# PowerSupply.net
KiCad netlist of a schematic drawn in Altium Designer
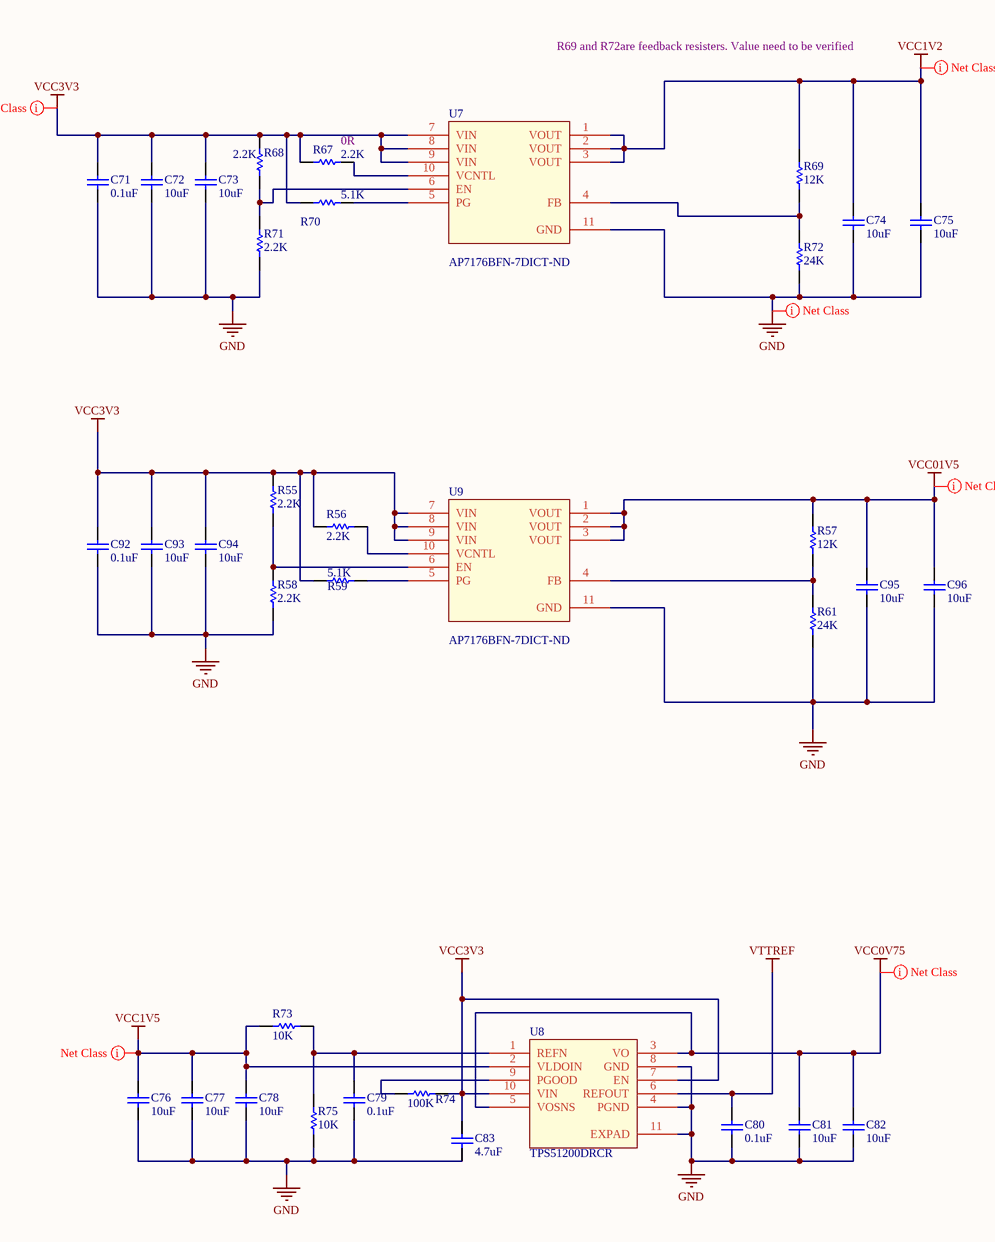
[diagram p0: PowerSupply.SchDoc]

(export (version "E")
  (design (tool "Eeschema 10.0.6"))
  (components
    (comp (ref "C71")
      (value "0.1uF")
      (footprint "0402")
      (description "Capacitor (Semiconductor SIM Model)")
      (fields (field (name "Comment") "Cap Semi") (field (name "PUBLISHER") "Altium Limited"))
      (libsource (lib "Miscellaneous Devices") (part "Cap Semi"))
    )
    (comp (ref "C72")
      (value "10uF")
      (footprint "1608[0603]")
      (description "Capacitor (Semiconductor SIM Model)")
      (fields (field (name "Comment") "Cap Semi") (field (name "PUBLISHER") "Altium Limited"))
      (libsource (lib "Miscellaneous Devices") (part "Cap Semi"))
    )
    (comp (ref "C73")
      (value "10uF")
      (footprint "1608[0603]")
      (description "Capacitor (Semiconductor SIM Model)")
      (fields (field (name "Comment") "Cap Semi") (field (name "PUBLISHER") "Altium Limited"))
      (libsource (lib "Miscellaneous Devices") (part "Cap Semi"))
    )
    (comp (ref "C74")
      (value "10uF")
      (footprint "C0805")
      (description "Capacitor (Semiconductor SIM Model)")
      (fields (field (name "Comment") "Cap Semi") (field (name "PUBLISHER") "Altium Limited"))
      (libsource (lib "Miscellaneous Devices") (part "Cap Semi"))
    )
    (comp (ref "C75")
      (value "10uF")
      (footprint "C0805")
      (description "Capacitor (Semiconductor SIM Model)")
      (fields (field (name "Comment") "Cap Semi") (field (name "PUBLISHER") "Altium Limited"))
      (libsource (lib "Miscellaneous Devices") (part "Cap Semi"))
    )
    (comp (ref "C76")
      (value "10uF")
      (footprint "1608[0603]")
      (description "Capacitor (Semiconductor SIM Model)")
      (fields (field (name "Comment") "Cap Semi") (field (name "PUBLISHER") "Altium Limited"))
      (libsource (lib "Miscellaneous Devices") (part "Cap Semi"))
    )
    (comp (ref "C77")
      (value "10uF")
      (footprint "1608[0603]")
      (description "Capacitor (Semiconductor SIM Model)")
      (fields (field (name "Comment") "Cap Semi") (field (name "PUBLISHER") "Altium Limited"))
      (libsource (lib "Miscellaneous Devices") (part "Cap Semi"))
    )
    (comp (ref "C78")
      (value "10uF")
      (footprint "0402")
      (description "Capacitor (Semiconductor SIM Model)")
      (fields (field (name "Comment") "Cap Semi") (field (name "PUBLISHER") "Altium Limited"))
      (libsource (lib "Miscellaneous Devices") (part "Cap Semi"))
    )
    (comp (ref "C79")
      (value "0.1uF")
      (footprint "0402")
      (description "Capacitor (Semiconductor SIM Model)")
      (fields (field (name "Comment") "Cap Semi") (field (name "PUBLISHER") "Altium Limited"))
      (libsource (lib "Miscellaneous Devices") (part "Cap Semi"))
    )
    (comp (ref "C80")
      (value "0.1uF")
      (footprint "0402")
      (description "Capacitor (Semiconductor SIM Model)")
      (fields (field (name "Comment") "Cap Semi") (field (name "PUBLISHER") "Altium Limited"))
      (libsource (lib "Miscellaneous Devices") (part "Cap Semi"))
    )
    (comp (ref "C81")
      (value "10uF")
      (footprint "0402")
      (description "Capacitor (Semiconductor SIM Model)")
      (fields (field (name "Comment") "Cap Semi") (field (name "PUBLISHER") "Altium Limited"))
      (libsource (lib "Miscellaneous Devices") (part "Cap Semi"))
    )
    (comp (ref "C82")
      (value "10uF")
      (footprint "C0805")
      (description "Capacitor (Semiconductor SIM Model)")
      (fields (field (name "Comment") "Cap Semi") (field (name "PUBLISHER") "Altium Limited"))
      (libsource (lib "Miscellaneous Devices") (part "Cap Semi"))
    )
    (comp (ref "C83")
      (value "4.7uF")
      (footprint "0402")
      (description "Capacitor (Semiconductor SIM Model)")
      (fields (field (name "Comment") "Cap Semi") (field (name "PUBLISHER") "Altium Limited"))
      (libsource (lib "Miscellaneous Devices") (part "Cap Semi"))
    )
    (comp (ref "C92")
      (value "0.1uF")
      (footprint "0402")
      (description "Capacitor")
      (fields (field (name "Comment") "Cap") (field (name "PUBLISHER") "Altium Limited"))
      (libsource (lib "Miscellaneous Devices") (part "Cap"))
    )
    (comp (ref "C93")
      (value "10uF")
      (footprint "1608[0603]")
      (description "Capacitor")
      (fields (field (name "Comment") "Cap") (field (name "PUBLISHER") "Altium Limited"))
      (libsource (lib "Miscellaneous Devices") (part "Cap"))
    )
    (comp (ref "C94")
      (value "10uF")
      (footprint "1608[0603]")
      (description "Capacitor")
      (fields (field (name "Comment") "Cap") (field (name "PUBLISHER") "Altium Limited"))
      (libsource (lib "Miscellaneous Devices") (part "Cap"))
    )
    (comp (ref "C95")
      (value "10uF")
      (footprint "1608[0603]")
      (description "Capacitor")
      (fields (field (name "Comment") "Cap") (field (name "PUBLISHER") "Altium Limited"))
      (libsource (lib "Miscellaneous Devices") (part "Cap"))
    )
    (comp (ref "C96")
      (value "10uF")
      (footprint "1608[0603]")
      (description "Capacitor")
      (fields (field (name "Comment") "Cap") (field (name "PUBLISHER") "Altium Limited"))
      (libsource (lib "Miscellaneous Devices") (part "Cap"))
    )
    (comp (ref "R55")
      (value "2.2K")
      (description "Semiconductor Resistor")
      (fields (field (name "Comment") "Res Semi") (field (name "PUBLISHER") "Altium Limited"))
      (libsource (lib "Miscellaneous Devices") (part "Res Semi"))
    )
    (comp (ref "R56")
      (value "2.2K")
      (description "Semiconductor Resistor")
      (fields (field (name "Comment") "Res Semi") (field (name "PUBLISHER") "Altium Limited"))
      (libsource (lib "Miscellaneous Devices") (part "Res Semi"))
    )
    (comp (ref "R57")
      (value "12K")
      (description "Semiconductor Resistor")
      (fields (field (name "Comment") "Res Semi") (field (name "PUBLISHER") "Altium Limited"))
      (libsource (lib "Miscellaneous Devices") (part "Res Semi"))
    )
    (comp (ref "R58")
      (value "2.2K")
      (description "Semiconductor Resistor")
      (fields (field (name "Comment") "Res Semi") (field (name "PUBLISHER") "Altium Limited"))
      (libsource (lib "Miscellaneous Devices") (part "Res Semi"))
    )
    (comp (ref "R59")
      (value "5.1K")
      (description "Semiconductor Resistor")
      (fields (field (name "Comment") "Res Semi") (field (name "PUBLISHER") "Altium Limited"))
      (libsource (lib "Miscellaneous Devices") (part "Res Semi"))
    )
    (comp (ref "R61")
      (value "24K")
      (description "Semiconductor Resistor")
      (fields (field (name "Comment") "Res Semi") (field (name "PUBLISHER") "Altium Limited"))
      (libsource (lib "Miscellaneous Devices") (part "Res Semi"))
    )
    (comp (ref "R67")
      (value "2.2K")
      (footprint "0402")
      (description "Semiconductor Resistor")
      (fields (field (name "Comment") "Res Semi") (field (name "PUBLISHER") "Altium Limited"))
      (libsource (lib "Miscellaneous Devices") (part "Res Semi"))
    )
    (comp (ref "R68")
      (value "2.2K")
      (footprint "0402")
      (description "Semiconductor Resistor")
      (fields (field (name "Comment") "Res Semi") (field (name "PUBLISHER") "Altium Limited"))
      (libsource (lib "Miscellaneous Devices") (part "Res Semi"))
    )
    (comp (ref "R69")
      (value "12K")
      (footprint "0402")
      (description "Semiconductor Resistor")
      (fields (field (name "Comment") "Res Semi") (field (name "PUBLISHER") "Altium Limited"))
      (libsource (lib "Miscellaneous Devices") (part "Res Semi"))
    )
    (comp (ref "R70")
      (value "5.1K")
      (footprint "0402")
      (description "Semiconductor Resistor")
      (fields (field (name "Comment") "Res Semi") (field (name "PUBLISHER") "Altium Limited"))
      (libsource (lib "Miscellaneous Devices") (part "Res Semi"))
    )
    (comp (ref "R71")
      (value "2.2K")
      (description "Semiconductor Resistor")
      (fields (field (name "Comment") "Res Semi") (field (name "PUBLISHER") "Altium Limited"))
      (libsource (lib "Miscellaneous Devices") (part "Res Semi"))
    )
    (comp (ref "R72")
      (value "24K")
      (footprint "0402")
      (description "Semiconductor Resistor")
      (fields (field (name "Comment") "Res Semi") (field (name "PUBLISHER") "Altium Limited"))
      (libsource (lib "Miscellaneous Devices") (part "Res Semi"))
    )
    (comp (ref "R73")
      (value "10K")
      (footprint "0402")
      (description "Semiconductor Resistor")
      (fields (field (name "Comment") "Res Semi") (field (name "PUBLISHER") "Altium Limited"))
      (libsource (lib "Miscellaneous Devices") (part "Res Semi"))
    )
    (comp (ref "R74")
      (value "100K")
      (footprint "0402")
      (description "Semiconductor Resistor")
      (fields (field (name "Comment") "Res Semi") (field (name "PUBLISHER") "Altium Limited"))
      (libsource (lib "Miscellaneous Devices") (part "Res Semi"))
    )
    (comp (ref "R75")
      (value "10K")
      (footprint "0402")
      (description "Semiconductor Resistor")
      (fields (field (name "Comment") "Res Semi") (field (name "PUBLISHER") "Altium Limited"))
      (libsource (lib "Miscellaneous Devices") (part "Res Semi"))
    )
    (comp (ref "U7")
      (value "AP7176BFN-7DICT-ND")
      (footprint "PSON50P300X100_HS-11N")
      (description "IC REG LDO ADJ 3A 10-DFN")
      (fields
        (field (name "MANUFACTURER") "Diodes Incorporated")
        (field (name "MANUFACTURER PART NUMBER") "AP7176BFN-7")
        (field (name "SUPPLIER PART NUMBER 1") "AP7176BFN-7DICT-ND")
      )
      (libsource (lib "PolySomeCrypto01") (part "AP7176BFN-7"))
    )
    (comp (ref "U8")
      (value "TPS51200DRCR")
      (footprint "PSON50P300X100_HS-11N")
      (description "IC CONV DDR DDR2 DDR3 10SON")
      (fields (field (name "MANUFACTURER") "Texas Instruments"))
      (libsource (lib "PolySomeCrypto01") (part "TPS51200DRCR"))
    )
    (comp (ref "U9")
      (value "AP7176BFN-7DICT-ND")
      (footprint "PSON50P300X100_HS-11N")
      (description "IC REG LDO ADJ 3A 10-DFN")
      (fields
        (field (name "MANUFACTURER") "Diodes Incorporated")
        (field (name "MANUFACTURER PART NUMBER") "AP7176BFN-7")
        (field (name "SUPPLIER PART NUMBER 1") "AP7176BFN-7DICT-ND")
      )
      (libsource (lib "PolySomeCrypto01") (part "AP7176BFN-7"))
    )
  )
  (nets
    (net (code "1") (name "GND") (class "Default")
      (node (ref "C71") (pin "2") (pinfunction "2_2") (pintype "passive"))
      (node (ref "C72") (pin "2") (pinfunction "2_2") (pintype "passive"))
      (node (ref "C73") (pin "2") (pinfunction "2_2") (pintype "passive"))
      (node (ref "C74") (pin "2") (pinfunction "2_2") (pintype "passive"))
      (node (ref "C75") (pin "2") (pinfunction "2_2") (pintype "passive"))
      (node (ref "C76") (pin "2") (pinfunction "2_2") (pintype "passive"))
      (node (ref "C77") (pin "2") (pinfunction "2_2") (pintype "passive"))
      (node (ref "C78") (pin "2") (pinfunction "2_2") (pintype "passive"))
      (node (ref "C79") (pin "2") (pinfunction "2_2") (pintype "passive"))
      (node (ref "C80") (pin "2") (pinfunction "2_2") (pintype "passive"))
      (node (ref "C81") (pin "2") (pinfunction "2_2") (pintype "passive"))
      (node (ref "C82") (pin "2") (pinfunction "2_2") (pintype "passive"))
      (node (ref "C83") (pin "2") (pinfunction "2_2") (pintype "passive"))
      (node (ref "C92") (pin "1") (pinfunction "1_1") (pintype "passive"))
      (node (ref "C93") (pin "1") (pinfunction "1_1") (pintype "passive"))
      (node (ref "C94") (pin "1") (pinfunction "1_1") (pintype "passive"))
      (node (ref "C95") (pin "1") (pinfunction "1_1") (pintype "passive"))
      (node (ref "C96") (pin "1") (pinfunction "1_1") (pintype "passive"))
      (node (ref "R58") (pin "1") (pinfunction "1_1") (pintype "passive"))
      (node (ref "R61") (pin "1") (pinfunction "1_1") (pintype "passive"))
      (node (ref "R71") (pin "1") (pinfunction "1_1") (pintype "passive"))
      (node (ref "R72") (pin "1") (pinfunction "1_1") (pintype "passive"))
      (node (ref "R75") (pin "1") (pinfunction "1_1") (pintype "passive"))
      (node (ref "U7") (pin "11") (pinfunction "GND_11") (pintype "power_in"))
      (node (ref "U8") (pin "11") (pinfunction "EXPAD_11") (pintype "power_in"))
      (node (ref "U8") (pin "4") (pinfunction "PGND_4") (pintype "power_in"))
      (node (ref "U8") (pin "8") (pinfunction "GND_8") (pintype "power_in"))
      (node (ref "U9") (pin "11") (pinfunction "GND_11") (pintype "power_in"))
    )
    (net (code "2") (name "Net-(U7-EN)") (class "Default")
      (node (ref "R68") (pin "1") (pinfunction "1_1") (pintype "passive"))
      (node (ref "R71") (pin "2") (pinfunction "2_2") (pintype "passive"))
      (node (ref "U7") (pin "6") (pinfunction "EN_6") (pintype "power_in"))
    )
    (net (code "3") (name "Net-(U7-FB)") (class "Default")
      (node (ref "R69") (pin "1") (pinfunction "1_1") (pintype "passive"))
      (node (ref "R72") (pin "2") (pinfunction "2_2") (pintype "passive"))
      (node (ref "U7") (pin "4") (pinfunction "FB_4") (pintype "power_in"))
    )
    (net (code "4") (name "Net-(U7-PG)") (class "Default")
      (node (ref "R70") (pin "2") (pinfunction "2_2") (pintype "passive"))
      (node (ref "U7") (pin "5") (pinfunction "PG_5") (pintype "open_collector"))
    )
    (net (code "5") (name "Net-(U7-VCNTL)") (class "Default")
      (node (ref "R67") (pin "2") (pinfunction "2_2") (pintype "passive"))
      (node (ref "U7") (pin "10") (pinfunction "VCNTL_10") (pintype "power_in"))
    )
    (net (code "6") (name "Net-(U8-PGOOD)") (class "Default")
      (node (ref "R74") (pin "1") (pinfunction "1_1") (pintype "passive"))
      (node (ref "U8") (pin "9") (pinfunction "PGOOD_9") (pintype "power_in"))
    )
    (net (code "7") (name "Net-(U8-REFN)") (class "Default")
      (node (ref "C79") (pin "1") (pinfunction "1_1") (pintype "passive"))
      (node (ref "R73") (pin "2") (pinfunction "2_2") (pintype "passive"))
      (node (ref "R75") (pin "2") (pinfunction "2_2") (pintype "passive"))
      (node (ref "U8") (pin "1") (pinfunction "REFN_1") (pintype "power_in"))
    )
    (net (code "8") (name "Net-(U9-EN)") (class "Default")
      (node (ref "R55") (pin "1") (pinfunction "1_1") (pintype "passive"))
      (node (ref "R58") (pin "2") (pinfunction "2_2") (pintype "passive"))
      (node (ref "U9") (pin "6") (pinfunction "EN_6") (pintype "power_in"))
    )
    (net (code "9") (name "Net-(U9-FB)") (class "Default")
      (node (ref "R57") (pin "1") (pinfunction "1_1") (pintype "passive"))
      (node (ref "R61") (pin "2") (pinfunction "2_2") (pintype "passive"))
      (node (ref "U9") (pin "4") (pinfunction "FB_4") (pintype "power_in"))
    )
    (net (code "10") (name "Net-(U9-PG)") (class "Default")
      (node (ref "R59") (pin "1") (pinfunction "1_1") (pintype "passive"))
      (node (ref "U9") (pin "5") (pinfunction "PG_5") (pintype "open_collector"))
    )
    (net (code "11") (name "Net-(U9-VCNTL)") (class "Default")
      (node (ref "R56") (pin "1") (pinfunction "1_1") (pintype "passive"))
      (node (ref "U9") (pin "10") (pinfunction "VCNTL_10") (pintype "power_in"))
    )
    (net (code "12") (name "VCC0V75") (class "Default")
      (node (ref "C81") (pin "1") (pinfunction "1_1") (pintype "passive"))
      (node (ref "C82") (pin "1") (pinfunction "1_1") (pintype "passive"))
      (node (ref "U8") (pin "3") (pinfunction "VO_3") (pintype "power_in"))
      (node (ref "U8") (pin "5") (pinfunction "VOSNS_5") (pintype "power_in"))
    )
    (net (code "13") (name "VCC1V2") (class "Default")
      (node (ref "C74") (pin "1") (pinfunction "1_1") (pintype "passive"))
      (node (ref "C75") (pin "1") (pinfunction "1_1") (pintype "passive"))
      (node (ref "R69") (pin "2") (pinfunction "2_2") (pintype "passive"))
      (node (ref "U7") (pin "1") (pinfunction "VOUT_1") (pintype "power_in"))
      (node (ref "U7") (pin "2") (pinfunction "VOUT_2") (pintype "power_in"))
      (node (ref "U7") (pin "3") (pinfunction "VOUT_3") (pintype "power_in"))
    )
    (net (code "14") (name "VCC1V5") (class "Default")
      (node (ref "C76") (pin "1") (pinfunction "1_1") (pintype "passive"))
      (node (ref "C77") (pin "1") (pinfunction "1_1") (pintype "passive"))
      (node (ref "C78") (pin "1") (pinfunction "1_1") (pintype "passive"))
      (node (ref "R73") (pin "1") (pinfunction "1_1") (pintype "passive"))
      (node (ref "U8") (pin "2") (pinfunction "VLDOIN_2") (pintype "power_in"))
    )
    (net (code "15") (name "VCC01V5") (class "Default")
      (node (ref "C95") (pin "2") (pinfunction "2_2") (pintype "passive"))
      (node (ref "C96") (pin "2") (pinfunction "2_2") (pintype "passive"))
      (node (ref "R57") (pin "2") (pinfunction "2_2") (pintype "passive"))
      (node (ref "U9") (pin "1") (pinfunction "VOUT_1") (pintype "power_in"))
      (node (ref "U9") (pin "2") (pinfunction "VOUT_2") (pintype "power_in"))
      (node (ref "U9") (pin "3") (pinfunction "VOUT_3") (pintype "power_in"))
    )
    (net (code "16") (name "VCC3V3") (class "Default")
      (node (ref "C71") (pin "1") (pinfunction "1_1") (pintype "passive"))
      (node (ref "C72") (pin "1") (pinfunction "1_1") (pintype "passive"))
      (node (ref "C73") (pin "1") (pinfunction "1_1") (pintype "passive"))
      (node (ref "C83") (pin "1") (pinfunction "1_1") (pintype "passive"))
      (node (ref "C92") (pin "2") (pinfunction "2_2") (pintype "passive"))
      (node (ref "C93") (pin "2") (pinfunction "2_2") (pintype "passive"))
      (node (ref "C94") (pin "2") (pinfunction "2_2") (pintype "passive"))
      (node (ref "R55") (pin "2") (pinfunction "2_2") (pintype "passive"))
      (node (ref "R56") (pin "2") (pinfunction "2_2") (pintype "passive"))
      (node (ref "R59") (pin "2") (pinfunction "2_2") (pintype "passive"))
      (node (ref "R67") (pin "1") (pinfunction "1_1") (pintype "passive"))
      (node (ref "R68") (pin "2") (pinfunction "2_2") (pintype "passive"))
      (node (ref "R70") (pin "1") (pinfunction "1_1") (pintype "passive"))
      (node (ref "R74") (pin "2") (pinfunction "2_2") (pintype "passive"))
      (node (ref "U7") (pin "7") (pinfunction "VIN_7") (pintype "power_in"))
      (node (ref "U7") (pin "8") (pinfunction "VIN_8") (pintype "power_in"))
      (node (ref "U7") (pin "9") (pinfunction "VIN_9") (pintype "power_in"))
      (node (ref "U8") (pin "10") (pinfunction "VIN_10") (pintype "power_in"))
      (node (ref "U8") (pin "7") (pinfunction "EN_7") (pintype "power_in"))
      (node (ref "U9") (pin "7") (pinfunction "VIN_7") (pintype "power_in"))
      (node (ref "U9") (pin "8") (pinfunction "VIN_8") (pintype "power_in"))
      (node (ref "U9") (pin "9") (pinfunction "VIN_9") (pintype "power_in"))
    )
    (net (code "17") (name "VTTREF") (class "Default")
      (node (ref "C80") (pin "1") (pinfunction "1_1") (pintype "passive"))
      (node (ref "U8") (pin "6") (pinfunction "REFOUT_6") (pintype "power_in"))
    )
  )
)
